# SCH-Button_LED_Sheet_1_Altium.net
KiCad netlist of a schematic drawn in Altium Designer
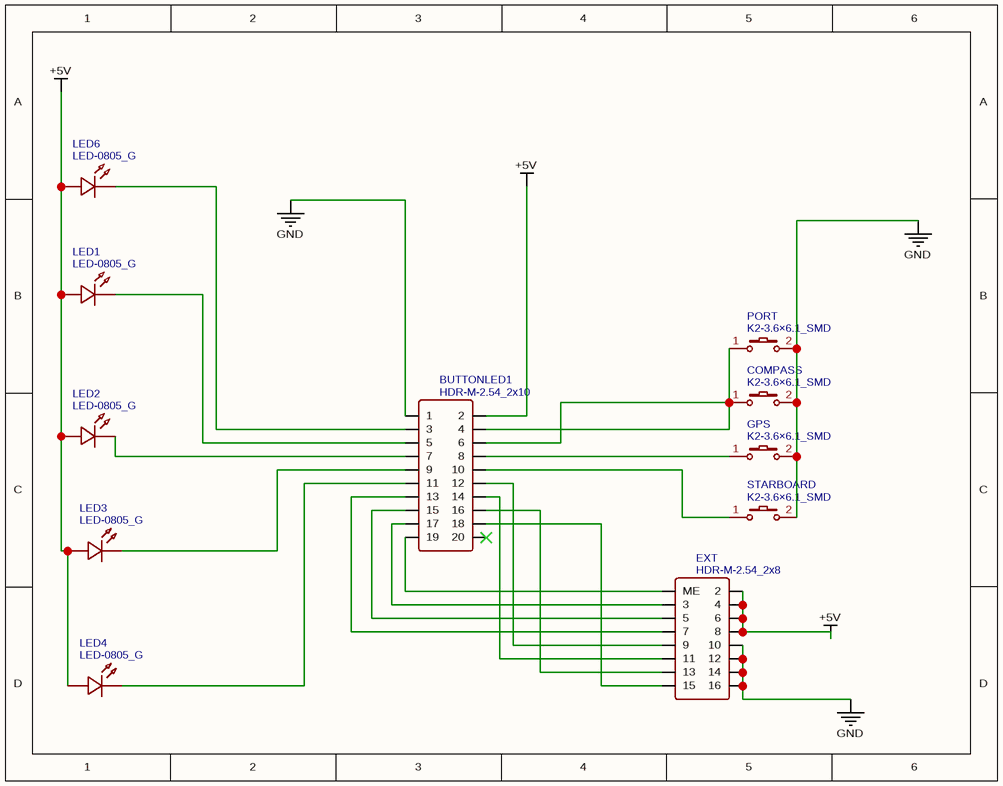
[diagram p0: SCH-Button_LED_Sheet_1_Altium.schdoc]

(export (version "E")
  (design (tool "Eeschema 10.0.6"))
  (components
    (comp (ref "BUTTONLED1")
      (value "HDR-M-2.54_2x10")
      (fields (field (name "CONTRIBUTOR") "LCEDA_Lib"))
      (libsource (lib "altium-import") (part "root_0_HDR-M-2.54_2x10_"))
    )
    (comp (ref "COMPASS")
      (value "K2-3.6×6.1_SMD")
      (fields (field (name "MANUFACTURER PART") "K2-1107ST-A4SW-06") (field (name "CONTRIBUTOR") "LCEDA_Lib"))
      (libsource (lib "altium-import") (part "root_0_K2-3.6×6.1_SMD_"))
    )
    (comp (ref "EXT")
      (value "HDR-M-2.54_2x8")
      (fields (field (name "CONTRIBUTOR") "LCEDA_Lib"))
      (libsource (lib "altium-import") (part "root_0_HDR-M-2.54_2x8_"))
    )
    (comp (ref "GPS")
      (value "K2-3.6×6.1_SMD")
      (fields (field (name "MANUFACTURER PART") "K2-1107ST-A4SW-06") (field (name "CONTRIBUTOR") "LCEDA_Lib"))
      (libsource (lib "altium-import") (part "root_0_K2-3.6×6.1_SMD_"))
    )
    (comp (ref "LED1")
      (value "LED-0805_G")
      (fields
        (field (name "MANUFACTURER") "国星光电")
        (field (name "MANUFACTURER PART") "NCD0805G1")
        (field (name "CONTRIBUTOR") "LCEDA_Lib")
      )
      (libsource (lib "altium-import") (part "root_0_LED-0805_G_"))
    )
    (comp (ref "LED2")
      (value "LED-0805_G")
      (fields
        (field (name "MANUFACTURER") "国星光电")
        (field (name "MANUFACTURER PART") "NCD0805G1")
        (field (name "CONTRIBUTOR") "LCEDA_Lib")
      )
      (libsource (lib "altium-import") (part "root_0_LED-0805_G_"))
    )
    (comp (ref "LED3")
      (value "LED-0805_G")
      (fields
        (field (name "MANUFACTURER") "国星光电")
        (field (name "MANUFACTURER PART") "NCD0805G1")
        (field (name "CONTRIBUTOR") "LCEDA_Lib")
      )
      (libsource (lib "altium-import") (part "root_0_LED-0805_G_"))
    )
    (comp (ref "LED4")
      (value "LED-0805_G")
      (fields
        (field (name "MANUFACTURER") "国星光电")
        (field (name "MANUFACTURER PART") "NCD0805G1")
        (field (name "CONTRIBUTOR") "LCEDA_Lib")
      )
      (libsource (lib "altium-import") (part "root_0_LED-0805_G_"))
    )
    (comp (ref "LED6")
      (value "LED-0805_G")
      (fields
        (field (name "MANUFACTURER") "国星光电")
        (field (name "MANUFACTURER PART") "NCD0805G1")
        (field (name "CONTRIBUTOR") "LCEDA_Lib")
      )
      (libsource (lib "altium-import") (part "root_0_LED-0805_G_"))
    )
    (comp (ref "PORT")
      (value "K2-3.6×6.1_SMD")
      (fields (field (name "MANUFACTURER PART") "K2-1107ST-A4SW-06") (field (name "CONTRIBUTOR") "LCEDA_Lib"))
      (libsource (lib "altium-import") (part "root_0_K2-3.6×6.1_SMD_"))
    )
    (comp (ref "STARBOARD")
      (value "K2-3.6×6.1_SMD")
      (fields (field (name "MANUFACTURER PART") "K2-1107ST-A4SW-06") (field (name "CONTRIBUTOR") "LCEDA_Lib"))
      (libsource (lib "altium-import") (part "root_0_K2-3.6×6.1_SMD_"))
    )
  )
  (nets
    (net (code "1") (name "+5V") (class "Default")
      (node (ref "BUTTONLED1") (pin "2") (pinfunction "2_2") (pintype "passive"))
      (node (ref "EXT") (pin "2") (pinfunction "2_2") (pintype "passive"))
      (node (ref "EXT") (pin "4") (pinfunction "4_4") (pintype "passive"))
      (node (ref "EXT") (pin "6") (pinfunction "6_6") (pintype "passive"))
      (node (ref "EXT") (pin "8") (pinfunction "8_8") (pintype "passive"))
      (node (ref "LED1") (pin "1") (pinfunction "1_1") (pintype "passive"))
      (node (ref "LED2") (pin "1") (pinfunction "1_1") (pintype "passive"))
      (node (ref "LED3") (pin "1") (pinfunction "1_1") (pintype "passive"))
      (node (ref "LED4") (pin "1") (pinfunction "1_1") (pintype "passive"))
      (node (ref "LED6") (pin "1") (pinfunction "1_1") (pintype "passive"))
    )
    (net (code "2") (name "GND") (class "Default")
      (node (ref "BUTTONLED1") (pin "1") (pinfunction "1_1") (pintype "passive"))
      (node (ref "COMPASS") (pin "2") (pinfunction "2_2") (pintype "passive"))
      (node (ref "EXT") (pin "10") (pinfunction "10_10") (pintype "passive"))
      (node (ref "EXT") (pin "12") (pinfunction "12_12") (pintype "passive"))
      (node (ref "EXT") (pin "14") (pinfunction "14_14") (pintype "passive"))
      (node (ref "EXT") (pin "16") (pinfunction "16_16") (pintype "passive"))
      (node (ref "GPS") (pin "2") (pinfunction "2_2") (pintype "passive"))
      (node (ref "PORT") (pin "2") (pinfunction "2_2") (pintype "passive"))
      (node (ref "STARBOARD") (pin "2") (pinfunction "2_2") (pintype "passive"))
    )
    (net (code "3") (name "Net-(BUTTONLED1-Pad3)") (class "Default")
      (node (ref "BUTTONLED1") (pin "3") (pinfunction "3_3") (pintype "passive"))
      (node (ref "LED6") (pin "2") (pinfunction "2_2") (pintype "passive"))
    )
    (net (code "4") (name "Net-(BUTTONLED1-Pad4)") (class "Default")
      (node (ref "BUTTONLED1") (pin "4") (pinfunction "4_4") (pintype "passive"))
      (node (ref "BUTTONLED1") (pin "6") (pinfunction "6_6") (pintype "passive"))
      (node (ref "COMPASS") (pin "1") (pinfunction "1_1") (pintype "passive"))
      (node (ref "PORT") (pin "1") (pinfunction "1_1") (pintype "passive"))
    )
    (net (code "5") (name "Net-(BUTTONLED1-Pad5)") (class "Default")
      (node (ref "BUTTONLED1") (pin "5") (pinfunction "5_5") (pintype "passive"))
      (node (ref "LED1") (pin "2") (pinfunction "2_2") (pintype "passive"))
    )
    (net (code "6") (name "Net-(BUTTONLED1-Pad7)") (class "Default")
      (node (ref "BUTTONLED1") (pin "7") (pinfunction "7_7") (pintype "passive"))
      (node (ref "LED2") (pin "2") (pinfunction "2_2") (pintype "passive"))
    )
    (net (code "7") (name "Net-(BUTTONLED1-Pad8)") (class "Default")
      (node (ref "BUTTONLED1") (pin "8") (pinfunction "8_8") (pintype "passive"))
      (node (ref "GPS") (pin "1") (pinfunction "1_1") (pintype "passive"))
    )
    (net (code "8") (name "Net-(BUTTONLED1-Pad9)") (class "Default")
      (node (ref "BUTTONLED1") (pin "9") (pinfunction "9_9") (pintype "passive"))
      (node (ref "LED3") (pin "2") (pinfunction "2_2") (pintype "passive"))
    )
    (net (code "9") (name "Net-(BUTTONLED1-Pad10)") (class "Default")
      (node (ref "BUTTONLED1") (pin "10") (pinfunction "10_10") (pintype "passive"))
      (node (ref "STARBOARD") (pin "1") (pinfunction "1_1") (pintype "passive"))
    )
    (net (code "10") (name "Net-(BUTTONLED1-Pad11)") (class "Default")
      (node (ref "BUTTONLED1") (pin "11") (pinfunction "11_11") (pintype "passive"))
      (node (ref "LED4") (pin "2") (pinfunction "2_2") (pintype "passive"))
    )
    (net (code "11") (name "Net-(BUTTONLED1-Pad12)") (class "Default")
      (node (ref "BUTTONLED1") (pin "12") (pinfunction "12_12") (pintype "passive"))
      (node (ref "EXT") (pin "9") (pinfunction "9_9") (pintype "passive"))
    )
    (net (code "12") (name "Net-(BUTTONLED1-Pad13)") (class "Default")
      (node (ref "BUTTONLED1") (pin "13") (pinfunction "13_13") (pintype "passive"))
      (node (ref "EXT") (pin "7") (pinfunction "7_7") (pintype "passive"))
    )
    (net (code "13") (name "Net-(BUTTONLED1-Pad14)") (class "Default")
      (node (ref "BUTTONLED1") (pin "14") (pinfunction "14_14") (pintype "passive"))
      (node (ref "EXT") (pin "11") (pinfunction "11_11") (pintype "passive"))
    )
    (net (code "14") (name "Net-(BUTTONLED1-Pad15)") (class "Default")
      (node (ref "BUTTONLED1") (pin "15") (pinfunction "15_15") (pintype "passive"))
      (node (ref "EXT") (pin "5") (pinfunction "5_5") (pintype "passive"))
    )
    (net (code "15") (name "Net-(BUTTONLED1-Pad16)") (class "Default")
      (node (ref "BUTTONLED1") (pin "16") (pinfunction "16_16") (pintype "passive"))
      (node (ref "EXT") (pin "13") (pinfunction "13_13") (pintype "passive"))
    )
    (net (code "16") (name "Net-(BUTTONLED1-Pad17)") (class "Default")
      (node (ref "BUTTONLED1") (pin "17") (pinfunction "17_17") (pintype "passive"))
      (node (ref "EXT") (pin "3") (pinfunction "3_3") (pintype "passive"))
    )
    (net (code "17") (name "Net-(BUTTONLED1-Pad18)") (class "Default")
      (node (ref "BUTTONLED1") (pin "18") (pinfunction "18_18") (pintype "passive"))
      (node (ref "EXT") (pin "15") (pinfunction "15_15") (pintype "passive"))
    )
    (net (code "18") (name "Net-(EXT-ME)") (class "Default")
      (node (ref "BUTTONLED1") (pin "19") (pinfunction "19_19") (pintype "passive"))
      (node (ref "EXT") (pin "1") (pinfunction "ME_1") (pintype "passive"))
    )
    (net (code "19") (name "unconnected-(BUTTONLED1-Pad20)") (class "Default")
      (node (ref "BUTTONLED1") (pin "20") (pinfunction "20_20") (pintype "passive+no_connect"))
    )
  )
)
